# Minimum_LPC2148.net
KiCad netlist of a schematic drawn in EAGLE
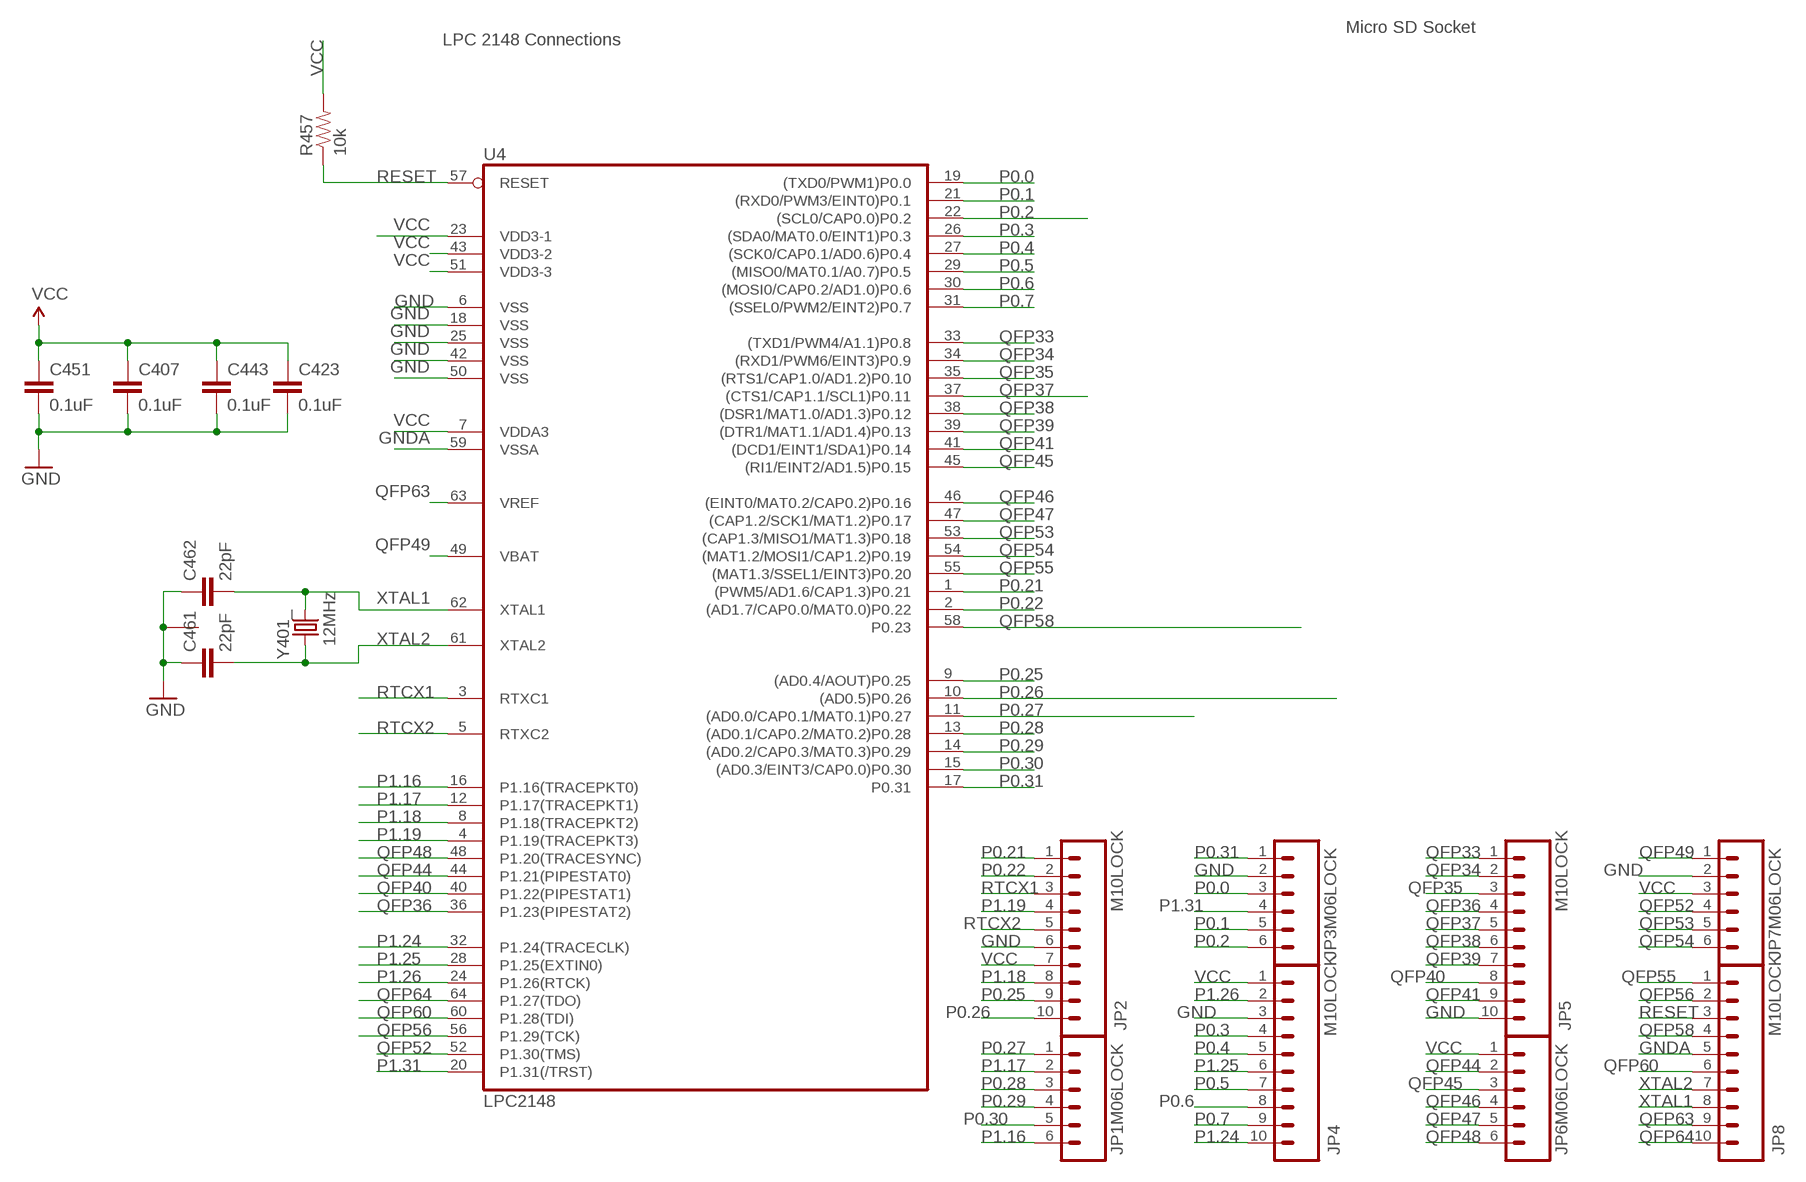
[diagram p0: schematic, sheet 1]

(export (version "E")
  (design (tool "Eeschema 10.0.6"))
  (components
    (comp (ref "C407")
      (value "0.1uF")
      (footprint "eagle-import:0402-CAP")
      (libsource (lib "eagle-import") (part "CAP0402-CAP"))
    )
    (comp (ref "C423")
      (value "0.1uF")
      (footprint "eagle-import:0402-CAP")
      (libsource (lib "eagle-import") (part "CAP0402-CAP"))
    )
    (comp (ref "C443")
      (value "0.1uF")
      (footprint "eagle-import:0402-CAP")
      (libsource (lib "eagle-import") (part "CAP0402-CAP"))
    )
    (comp (ref "C451")
      (value "0.1uF")
      (footprint "eagle-import:0402-CAP")
      (libsource (lib "eagle-import") (part "CAP0402-CAP"))
    )
    (comp (ref "C461")
      (value "22pF")
      (footprint "eagle-import:0402-CAP")
      (libsource (lib "eagle-import") (part "CAP0402-CAP"))
    )
    (comp (ref "C462")
      (value "22pF")
      (footprint "eagle-import:0402-CAP")
      (libsource (lib "eagle-import") (part "CAP0402-CAP"))
    )
    (comp (ref "JP1")
      (value "M06LOCK")
      (footprint "eagle-import:1X06_LOCK")
      (libsource (lib "eagle-import") (part "M06LOCK"))
    )
    (comp (ref "JP2")
      (value "M10LOCK")
      (footprint "eagle-import:1X10_LOCK")
      (libsource (lib "eagle-import") (part "M10LOCK"))
    )
    (comp (ref "JP3")
      (value "M06LOCK")
      (footprint "eagle-import:1X06_LOCK")
      (libsource (lib "eagle-import") (part "M06LOCK"))
    )
    (comp (ref "JP4")
      (value "M10LOCK")
      (footprint "eagle-import:1X10_LOCK")
      (libsource (lib "eagle-import") (part "M10LOCK"))
    )
    (comp (ref "JP5")
      (value "M10LOCK")
      (footprint "eagle-import:1X10_LOCK")
      (libsource (lib "eagle-import") (part "M10LOCK"))
    )
    (comp (ref "JP6")
      (value "M06LOCK")
      (footprint "eagle-import:1X06_LOCK")
      (libsource (lib "eagle-import") (part "M06LOCK"))
    )
    (comp (ref "JP7")
      (value "M06LOCK")
      (footprint "eagle-import:1X06_LOCK")
      (libsource (lib "eagle-import") (part "M06LOCK"))
    )
    (comp (ref "JP8")
      (value "M10LOCK")
      (footprint "eagle-import:1X10_LOCK")
      (libsource (lib "eagle-import") (part "M10LOCK"))
    )
    (comp (ref "R457")
      (value "10k")
      (footprint "eagle-import:0402-RES")
      (libsource (lib "eagle-import") (part "RESISTOR0402-RES"))
    )
    (comp (ref "U4")
      (value "LPC2148")
      (footprint "eagle-import:SQFP-S-10X10-64")
      (libsource (lib "eagle-import") (part "LPC213X"))
    )
    (comp (ref "Y401")
      (value "12MHz")
      (footprint "eagle-import:CRYSTAL_SMD")
      (libsource (lib "eagle-import") (part "TSX-3225"))
    )
  )
  (nets
    (net (code "1") (name "/GNDA") (class "Default")
      (node (ref "JP8") (pin "5") (pinfunction "5_5") (pintype "passive"))
      (node (ref "U4") (pin "59") (pinfunction "VSSA_59") (pintype "power_in"))
    )
    (net (code "2") (name "/P0.0") (class "Default")
      (node (ref "JP3") (pin "3") (pinfunction "3_3") (pintype "passive"))
      (node (ref "U4") (pin "19") (pinfunction "(TXD0/PWM1)P0.0_19") (pintype "bidirectional"))
    )
    (net (code "3") (name "/P0.1") (class "Default")
      (node (ref "JP3") (pin "5") (pinfunction "5_5") (pintype "passive"))
      (node (ref "U4") (pin "21") (pinfunction "(RXD0/PWM3/EINT0)P0.1_21") (pintype "bidirectional"))
    )
    (net (code "4") (name "/P0.2") (class "Default")
      (node (ref "JP3") (pin "6") (pinfunction "6_6") (pintype "passive"))
      (node (ref "U4") (pin "22") (pinfunction "(SCL0/CAP0.0)P0.2_22") (pintype "bidirectional"))
    )
    (net (code "5") (name "/P0.3") (class "Default")
      (node (ref "JP4") (pin "4") (pinfunction "4_4") (pintype "passive"))
      (node (ref "U4") (pin "26") (pinfunction "(SDA0/MAT0.0/EINT1)P0.3_26") (pintype "bidirectional"))
    )
    (net (code "6") (name "/P0.4") (class "Default")
      (node (ref "JP4") (pin "5") (pinfunction "5_5") (pintype "passive"))
      (node (ref "U4") (pin "27") (pinfunction "(SCK0/CAP0.1/AD0.6)P0.4_27") (pintype "bidirectional"))
    )
    (net (code "7") (name "/P0.5") (class "Default")
      (node (ref "JP4") (pin "7") (pinfunction "7_7") (pintype "passive"))
      (node (ref "U4") (pin "29") (pinfunction "(MISO0/MAT0.1/A0.7)P0.5_29") (pintype "bidirectional"))
    )
    (net (code "8") (name "/P0.6") (class "Default")
      (node (ref "JP4") (pin "8") (pinfunction "8_8") (pintype "passive"))
      (node (ref "U4") (pin "30") (pinfunction "(MOSI0/CAP0.2/AD1.0)P0.6_30") (pintype "bidirectional"))
    )
    (net (code "9") (name "/P0.7") (class "Default")
      (node (ref "JP4") (pin "9") (pinfunction "9_9") (pintype "passive"))
      (node (ref "U4") (pin "31") (pinfunction "(SSEL0/PWM2/EINT2)P0.7_31") (pintype "bidirectional"))
    )
    (net (code "10") (name "/P0.21") (class "Default")
      (node (ref "JP2") (pin "1") (pinfunction "1_1") (pintype "passive"))
      (node (ref "U4") (pin "1") (pinfunction "(PWM5/AD1.6/CAP1.3)P0.21_1") (pintype "bidirectional"))
    )
    (net (code "11") (name "/P0.22") (class "Default")
      (node (ref "JP2") (pin "2") (pinfunction "2_2") (pintype "passive"))
      (node (ref "U4") (pin "2") (pinfunction "(AD1.7/CAP0.0/MAT0.0)P0.22_2") (pintype "bidirectional"))
    )
    (net (code "12") (name "/P0.25") (class "Default")
      (node (ref "JP2") (pin "9") (pinfunction "9_9") (pintype "passive"))
      (node (ref "U4") (pin "9") (pinfunction "(AD0.4/AOUT)P0.25_9") (pintype "bidirectional"))
    )
    (net (code "13") (name "/P0.26") (class "Default")
      (node (ref "JP2") (pin "10") (pinfunction "10_10") (pintype "passive"))
      (node (ref "U4") (pin "10") (pinfunction "(AD0.5)P0.26_10") (pintype "bidirectional"))
    )
    (net (code "14") (name "/P0.27") (class "Default")
      (node (ref "JP1") (pin "1") (pinfunction "1_1") (pintype "passive"))
      (node (ref "U4") (pin "11") (pinfunction "(AD0.0/CAP0.1/MAT0.1)P0.27_11") (pintype "bidirectional"))
    )
    (net (code "15") (name "/P0.28") (class "Default")
      (node (ref "JP1") (pin "3") (pinfunction "3_3") (pintype "passive"))
      (node (ref "U4") (pin "13") (pinfunction "(AD0.1/CAP0.2/MAT0.2)P0.28_13") (pintype "bidirectional"))
    )
    (net (code "16") (name "/P0.29") (class "Default")
      (node (ref "JP1") (pin "4") (pinfunction "4_4") (pintype "passive"))
      (node (ref "U4") (pin "14") (pinfunction "(AD0.2/CAP0.3/MAT0.3)P0.29_14") (pintype "bidirectional"))
    )
    (net (code "17") (name "/P0.30") (class "Default")
      (node (ref "JP1") (pin "5") (pinfunction "5_5") (pintype "passive"))
      (node (ref "U4") (pin "15") (pinfunction "(AD0.3/EINT3/CAP0.0)P0.30_15") (pintype "bidirectional"))
    )
    (net (code "18") (name "/P0.31") (class "Default")
      (node (ref "JP3") (pin "1") (pinfunction "1_1") (pintype "passive"))
      (node (ref "U4") (pin "17") (pinfunction "P0.31_17") (pintype "output"))
    )
    (net (code "19") (name "/P1.16") (class "Default")
      (node (ref "JP1") (pin "6") (pinfunction "6_6") (pintype "passive"))
      (node (ref "U4") (pin "16") (pinfunction "P1.16(TRACEPKT0)_16") (pintype "bidirectional"))
    )
    (net (code "20") (name "/P1.17") (class "Default")
      (node (ref "JP1") (pin "2") (pinfunction "2_2") (pintype "passive"))
      (node (ref "U4") (pin "12") (pinfunction "P1.17(TRACEPKT1)_12") (pintype "bidirectional"))
    )
    (net (code "21") (name "/P1.18") (class "Default")
      (node (ref "JP2") (pin "8") (pinfunction "8_8") (pintype "passive"))
      (node (ref "U4") (pin "8") (pinfunction "P1.18(TRACEPKT2)_8") (pintype "bidirectional"))
    )
    (net (code "22") (name "/P1.19") (class "Default")
      (node (ref "JP2") (pin "4") (pinfunction "4_4") (pintype "passive"))
      (node (ref "U4") (pin "4") (pinfunction "P1.19(TRACEPKT3)_4") (pintype "bidirectional"))
    )
    (net (code "23") (name "/P1.24") (class "Default")
      (node (ref "JP4") (pin "10") (pinfunction "10_10") (pintype "passive"))
      (node (ref "U4") (pin "32") (pinfunction "P1.24(TRACECLK)_32") (pintype "bidirectional"))
    )
    (net (code "24") (name "/P1.25") (class "Default")
      (node (ref "JP4") (pin "6") (pinfunction "6_6") (pintype "passive"))
      (node (ref "U4") (pin "28") (pinfunction "P1.25(EXTIN0)_28") (pintype "bidirectional"))
    )
    (net (code "25") (name "/P1.26") (class "Default")
      (node (ref "JP4") (pin "2") (pinfunction "2_2") (pintype "passive"))
      (node (ref "U4") (pin "24") (pinfunction "P1.26(RTCK)_24") (pintype "bidirectional"))
    )
    (net (code "26") (name "/P1.31") (class "Default")
      (node (ref "JP3") (pin "4") (pinfunction "4_4") (pintype "passive"))
      (node (ref "U4") (pin "20") (pinfunction "P1.31(/TRST)_20") (pintype "bidirectional"))
    )
    (net (code "27") (name "/QFP33") (class "Default")
      (node (ref "JP5") (pin "1") (pinfunction "1_1") (pintype "passive"))
      (node (ref "U4") (pin "33") (pinfunction "(TXD1/PWM4/A1.1)P0.8_33") (pintype "bidirectional"))
    )
    (net (code "28") (name "/QFP34") (class "Default")
      (node (ref "JP5") (pin "2") (pinfunction "2_2") (pintype "passive"))
      (node (ref "U4") (pin "34") (pinfunction "(RXD1/PWM6/EINT3)P0.9_34") (pintype "bidirectional"))
    )
    (net (code "29") (name "/QFP35") (class "Default")
      (node (ref "JP5") (pin "3") (pinfunction "3_3") (pintype "passive"))
      (node (ref "U4") (pin "35") (pinfunction "(RTS1/CAP1.0/AD1.2)P0.10_35") (pintype "bidirectional"))
    )
    (net (code "30") (name "/QFP36") (class "Default")
      (node (ref "JP5") (pin "4") (pinfunction "4_4") (pintype "passive"))
      (node (ref "U4") (pin "36") (pinfunction "P1.23(PIPESTAT2)_36") (pintype "bidirectional"))
    )
    (net (code "31") (name "/QFP37") (class "Default")
      (node (ref "JP5") (pin "5") (pinfunction "5_5") (pintype "passive"))
      (node (ref "U4") (pin "37") (pinfunction "(CTS1/CAP1.1/SCL1)P0.11_37") (pintype "bidirectional"))
    )
    (net (code "32") (name "/QFP38") (class "Default")
      (node (ref "JP5") (pin "6") (pinfunction "6_6") (pintype "passive"))
      (node (ref "U4") (pin "38") (pinfunction "(DSR1/MAT1.0/AD1.3)P0.12_38") (pintype "bidirectional"))
    )
    (net (code "33") (name "/QFP39") (class "Default")
      (node (ref "JP5") (pin "7") (pinfunction "7_7") (pintype "passive"))
      (node (ref "U4") (pin "39") (pinfunction "(DTR1/MAT1.1/AD1.4)P0.13_39") (pintype "bidirectional"))
    )
    (net (code "34") (name "/QFP40") (class "Default")
      (node (ref "JP5") (pin "8") (pinfunction "8_8") (pintype "passive"))
      (node (ref "U4") (pin "40") (pinfunction "P1.22(PIPESTAT1)_40") (pintype "bidirectional"))
    )
    (net (code "35") (name "/QFP41") (class "Default")
      (node (ref "JP5") (pin "9") (pinfunction "9_9") (pintype "passive"))
      (node (ref "U4") (pin "41") (pinfunction "(DCD1/EINT1/SDA1)P0.14_41") (pintype "bidirectional"))
    )
    (net (code "36") (name "/QFP44") (class "Default")
      (node (ref "JP6") (pin "2") (pinfunction "2_2") (pintype "passive"))
      (node (ref "U4") (pin "44") (pinfunction "P1.21(PIPESTAT0)_44") (pintype "bidirectional"))
    )
    (net (code "37") (name "/QFP45") (class "Default")
      (node (ref "JP6") (pin "3") (pinfunction "3_3") (pintype "passive"))
      (node (ref "U4") (pin "45") (pinfunction "(RI1/EINT2/AD1.5)P0.15_45") (pintype "bidirectional"))
    )
    (net (code "38") (name "/QFP46") (class "Default")
      (node (ref "JP6") (pin "4") (pinfunction "4_4") (pintype "passive"))
      (node (ref "U4") (pin "46") (pinfunction "(EINT0/MAT0.2/CAP0.2)P0.16_46") (pintype "bidirectional"))
    )
    (net (code "39") (name "/QFP47") (class "Default")
      (node (ref "JP6") (pin "5") (pinfunction "5_5") (pintype "passive"))
      (node (ref "U4") (pin "47") (pinfunction "(CAP1.2/SCK1/MAT1.2)P0.17_47") (pintype "bidirectional"))
    )
    (net (code "40") (name "/QFP48") (class "Default")
      (node (ref "JP6") (pin "6") (pinfunction "6_6") (pintype "passive"))
      (node (ref "U4") (pin "48") (pinfunction "P1.20(TRACESYNC)_48") (pintype "bidirectional"))
    )
    (net (code "41") (name "/QFP49") (class "Default")
      (node (ref "JP7") (pin "1") (pinfunction "1_1") (pintype "passive"))
      (node (ref "U4") (pin "49") (pinfunction "VBAT_49") (pintype "power_in"))
    )
    (net (code "42") (name "/QFP52") (class "Default")
      (node (ref "JP7") (pin "4") (pinfunction "4_4") (pintype "passive"))
      (node (ref "U4") (pin "52") (pinfunction "P1.30(TMS)_52") (pintype "bidirectional"))
    )
    (net (code "43") (name "/QFP53") (class "Default")
      (node (ref "JP7") (pin "5") (pinfunction "5_5") (pintype "passive"))
      (node (ref "U4") (pin "53") (pinfunction "(CAP1.3/MISO1/MAT1.3)P0.18_53") (pintype "bidirectional"))
    )
    (net (code "44") (name "/QFP54") (class "Default")
      (node (ref "JP7") (pin "6") (pinfunction "6_6") (pintype "passive"))
      (node (ref "U4") (pin "54") (pinfunction "(MAT1.2/MOSI1/CAP1.2)P0.19_54") (pintype "bidirectional"))
    )
    (net (code "45") (name "/QFP55") (class "Default")
      (node (ref "JP8") (pin "1") (pinfunction "1_1") (pintype "passive"))
      (node (ref "U4") (pin "55") (pinfunction "(MAT1.3/SSEL1/EINT3)P0.20_55") (pintype "bidirectional"))
    )
    (net (code "46") (name "/QFP56") (class "Default")
      (node (ref "JP8") (pin "2") (pinfunction "2_2") (pintype "passive"))
      (node (ref "U4") (pin "56") (pinfunction "P1.29(TCK)_56") (pintype "bidirectional"))
    )
    (net (code "47") (name "/QFP58") (class "Default")
      (node (ref "JP8") (pin "4") (pinfunction "4_4") (pintype "passive"))
      (node (ref "U4") (pin "58") (pinfunction "P0.23_58") (pintype "bidirectional"))
    )
    (net (code "48") (name "/QFP60") (class "Default")
      (node (ref "JP8") (pin "6") (pinfunction "6_6") (pintype "passive"))
      (node (ref "U4") (pin "60") (pinfunction "P1.28(TDI)_60") (pintype "bidirectional"))
    )
    (net (code "49") (name "/QFP63") (class "Default")
      (node (ref "JP8") (pin "9") (pinfunction "9_9") (pintype "passive"))
      (node (ref "U4") (pin "63") (pinfunction "VREF_63") (pintype "input"))
    )
    (net (code "50") (name "/QFP64") (class "Default")
      (node (ref "JP8") (pin "10") (pinfunction "10_10") (pintype "passive"))
      (node (ref "U4") (pin "64") (pinfunction "P1.27(TDO)_64") (pintype "bidirectional"))
    )
    (net (code "51") (name "/RESET") (class "Default")
      (node (ref "JP8") (pin "3") (pinfunction "3_3") (pintype "passive"))
      (node (ref "R457") (pin "1") (pinfunction "1_1") (pintype "passive"))
      (node (ref "U4") (pin "57") (pinfunction "RESET_57") (pintype "input"))
    )
    (net (code "52") (name "/RTCX1") (class "Default")
      (node (ref "JP2") (pin "3") (pinfunction "3_3") (pintype "passive"))
      (node (ref "U4") (pin "3") (pinfunction "RTXC1_3") (pintype "input"))
    )
    (net (code "53") (name "/RTCX2") (class "Default")
      (node (ref "JP2") (pin "5") (pinfunction "5_5") (pintype "passive"))
      (node (ref "U4") (pin "5") (pinfunction "RTXC2_5") (pintype "output"))
    )
    (net (code "54") (name "/XTAL1") (class "Default")
      (node (ref "C462") (pin "2") (pinfunction "2_2") (pintype "passive"))
      (node (ref "JP8") (pin "8") (pinfunction "8_8") (pintype "passive"))
      (node (ref "U4") (pin "62") (pinfunction "XTAL1_62") (pintype "input"))
      (node (ref "Y401") (pin "3") (pinfunction "2_3") (pintype "passive"))
    )
    (net (code "55") (name "/XTAL2") (class "Default")
      (node (ref "C461") (pin "2") (pinfunction "2_2") (pintype "passive"))
      (node (ref "JP8") (pin "7") (pinfunction "7_7") (pintype "passive"))
      (node (ref "U4") (pin "61") (pinfunction "XTAL2_61") (pintype "output"))
      (node (ref "Y401") (pin "1") (pinfunction "1_1") (pintype "passive"))
    )
    (net (code "56") (name "GND") (class "Default")
      (node (ref "C407") (pin "2") (pinfunction "2_2") (pintype "passive"))
      (node (ref "C423") (pin "2") (pinfunction "2_2") (pintype "passive"))
      (node (ref "C443") (pin "2") (pinfunction "2_2") (pintype "passive"))
      (node (ref "C451") (pin "2") (pinfunction "2_2") (pintype "passive"))
      (node (ref "C461") (pin "1") (pinfunction "1_1") (pintype "passive"))
      (node (ref "C462") (pin "1") (pinfunction "1_1") (pintype "passive"))
      (node (ref "JP2") (pin "6") (pinfunction "6_6") (pintype "passive"))
      (node (ref "JP3") (pin "2") (pinfunction "2_2") (pintype "passive"))
      (node (ref "JP4") (pin "3") (pinfunction "3_3") (pintype "passive"))
      (node (ref "JP5") (pin "10") (pinfunction "10_10") (pintype "passive"))
      (node (ref "JP7") (pin "2") (pinfunction "2_2") (pintype "passive"))
      (node (ref "U4") (pin "18") (pinfunction "VSS_18") (pintype "power_in"))
      (node (ref "U4") (pin "25") (pinfunction "VSS_25") (pintype "power_in"))
      (node (ref "U4") (pin "42") (pinfunction "VSS_42") (pintype "power_in"))
      (node (ref "U4") (pin "50") (pinfunction "VSS_50") (pintype "power_in"))
      (node (ref "U4") (pin "6") (pinfunction "VSS_6") (pintype "power_in"))
      (node (ref "Y401") (pin "2") (pinfunction "1_2") (pintype "bidirectional"))
      (node (ref "Y401") (pin "4") (pinfunction "1_4") (pintype "bidirectional"))
    )
    (net (code "57") (name "VCC") (class "Default")
      (node (ref "C407") (pin "1") (pinfunction "1_1") (pintype "passive"))
      (node (ref "C423") (pin "1") (pinfunction "1_1") (pintype "passive"))
      (node (ref "C443") (pin "1") (pinfunction "1_1") (pintype "passive"))
      (node (ref "C451") (pin "1") (pinfunction "1_1") (pintype "passive"))
      (node (ref "JP2") (pin "7") (pinfunction "7_7") (pintype "passive"))
      (node (ref "JP4") (pin "1") (pinfunction "1_1") (pintype "passive"))
      (node (ref "JP6") (pin "1") (pinfunction "1_1") (pintype "passive"))
      (node (ref "JP7") (pin "3") (pinfunction "3_3") (pintype "passive"))
      (node (ref "R457") (pin "2") (pinfunction "2_2") (pintype "passive"))
      (node (ref "U4") (pin "23") (pinfunction "VDD3-1_23") (pintype "power_in"))
      (node (ref "U4") (pin "43") (pinfunction "VDD3-2_43") (pintype "power_in"))
      (node (ref "U4") (pin "51") (pinfunction "VDD3-3_51") (pintype "power_in"))
      (node (ref "U4") (pin "7") (pinfunction "VDDA3_7") (pintype "power_in"))
    )
  )
)
